# tick-display-mk-4-mini.net
KiCad netlist of a schematic drawn in EAGLE
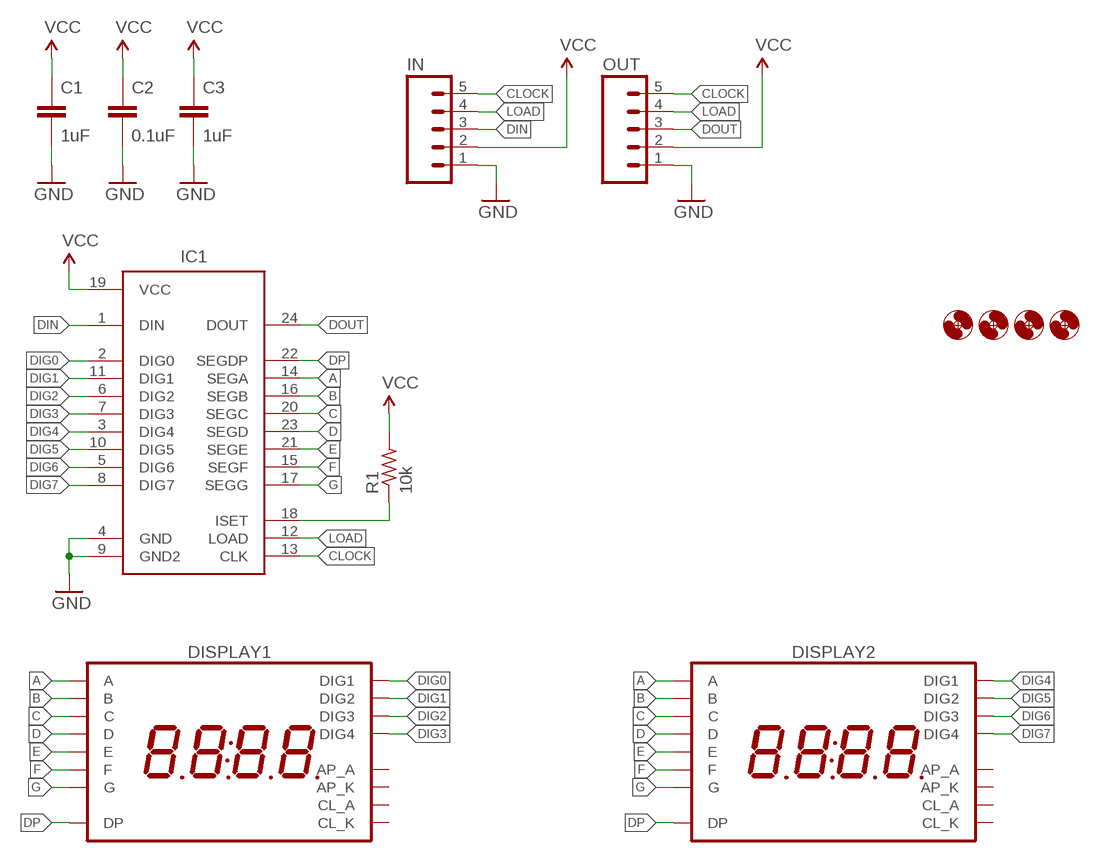
[diagram p0: schematic, sheet 1]

(export (version "E")
  (design (tool "Eeschema 10.0.6"))
  (components
    (comp (ref "C1")
      (value "1uF")
      (footprint "eagle-import:C025-024X044")
      (libsource (lib "eagle-import") (part "CAPACITOR-CERAMIC025-024X044"))
    )
    (comp (ref "C2")
      (value "0.1uF")
      (footprint "eagle-import:C025-024X044")
      (libsource (lib "eagle-import") (part "CAPACITOR-CERAMIC025-024X044"))
    )
    (comp (ref "C3")
      (value "1uF")
      (footprint "eagle-import:C025-024X044")
      (libsource (lib "eagle-import") (part "CAPACITOR-CERAMIC025-024X044"))
    )
    (comp (ref "DISPLAY1")
      (value "7SEG_4DIGIT_10MM")
      (footprint "eagle-import:7SEG_4DIG_10MM")
      (libsource (lib "eagle-import") (part "7SEG_4DIGIT_10MM"))
    )
    (comp (ref "DISPLAY2")
      (value "7SEG_4DIGIT_10MM")
      (footprint "eagle-import:7SEG_4DIG_10MM")
      (libsource (lib "eagle-import") (part "7SEG_4DIGIT_10MM"))
    )
    (comp (ref "H1")
      (value "HOLE#2")
      (footprint "eagle-import:HOLE-#2")
      (libsource (lib "eagle-import") (part "HOLE#2"))
    )
    (comp (ref "H2")
      (value "HOLE#2")
      (footprint "eagle-import:HOLE-#2")
      (libsource (lib "eagle-import") (part "HOLE#2"))
    )
    (comp (ref "H3")
      (value "HOLE#2")
      (footprint "eagle-import:HOLE-#2")
      (libsource (lib "eagle-import") (part "HOLE#2"))
    )
    (comp (ref "H4")
      (value "HOLE#2")
      (footprint "eagle-import:HOLE-#2")
      (libsource (lib "eagle-import") (part "HOLE#2"))
    )
    (comp (ref "IC1")
      (value "MAX7219DIP")
      (footprint "eagle-import:DIL24")
      (libsource (lib "eagle-import") (part "MAX7219DIP"))
    )
    (comp (ref "IN")
      (value "M05PTH")
      (footprint "eagle-import:1X05")
      (libsource (lib "eagle-import") (part "M05PTH"))
    )
    (comp (ref "OUT")
      (value "M05PTH")
      (footprint "eagle-import:1X05")
      (libsource (lib "eagle-import") (part "M05PTH"))
    )
    (comp (ref "R1")
      (value "10k")
      (footprint "eagle-import:RESISTOR-AXIAL-PTH-7.68MM")
      (libsource (lib "eagle-import") (part "RESISTORPTH-AXIAL-7.68MM"))
    )
  )
  (nets
    (net (code "1") (name "A") (class "Default")
      (node (ref "DISPLAY1") (pin "14") (pinfunction "A_14") (pintype "passive"))
      (node (ref "DISPLAY2") (pin "14") (pinfunction "A_14") (pintype "passive"))
      (node (ref "IC1") (pin "14") (pinfunction "SEGA_14") (pintype "bidirectional"))
    )
    (net (code "2") (name "B") (class "Default")
      (node (ref "DISPLAY1") (pin "16") (pinfunction "B_16") (pintype "passive"))
      (node (ref "DISPLAY2") (pin "16") (pinfunction "B_16") (pintype "passive"))
      (node (ref "IC1") (pin "16") (pinfunction "SEGB_16") (pintype "bidirectional"))
    )
    (net (code "3") (name "C") (class "Default")
      (node (ref "DISPLAY1") (pin "13") (pinfunction "C_13") (pintype "passive"))
      (node (ref "DISPLAY2") (pin "13") (pinfunction "C_13") (pintype "passive"))
      (node (ref "IC1") (pin "20") (pinfunction "SEGC_20") (pintype "bidirectional"))
    )
    (net (code "4") (name "CLOCK") (class "Default")
      (node (ref "IC1") (pin "13") (pinfunction "CLK_13") (pintype "bidirectional"))
      (node (ref "IN") (pin "5") (pinfunction "5_5") (pintype "passive"))
      (node (ref "OUT") (pin "5") (pinfunction "5_5") (pintype "passive"))
    )
    (net (code "5") (name "D") (class "Default")
      (node (ref "DISPLAY1") (pin "3") (pinfunction "D_3") (pintype "passive"))
      (node (ref "DISPLAY2") (pin "3") (pinfunction "D_3") (pintype "passive"))
      (node (ref "IC1") (pin "23") (pinfunction "SEGD_23") (pintype "bidirectional"))
    )
    (net (code "6") (name "DIG0") (class "Default")
      (node (ref "DISPLAY1") (pin "1") (pinfunction "DIG1_1") (pintype "passive"))
      (node (ref "IC1") (pin "2") (pinfunction "DIG0_2") (pintype "bidirectional"))
    )
    (net (code "7") (name "DIG1") (class "Default")
      (node (ref "DISPLAY1") (pin "2") (pinfunction "DIG2_2") (pintype "passive"))
      (node (ref "IC1") (pin "11") (pinfunction "DIG1_11") (pintype "bidirectional"))
    )
    (net (code "8") (name "DIG2") (class "Default")
      (node (ref "DISPLAY1") (pin "6") (pinfunction "DIG3_6") (pintype "passive"))
      (node (ref "IC1") (pin "6") (pinfunction "DIG2_6") (pintype "bidirectional"))
    )
    (net (code "9") (name "DIG3") (class "Default")
      (node (ref "DISPLAY1") (pin "8") (pinfunction "DIG4_8") (pintype "passive"))
      (node (ref "IC1") (pin "7") (pinfunction "DIG3_7") (pintype "bidirectional"))
    )
    (net (code "10") (name "DIG4") (class "Default")
      (node (ref "DISPLAY2") (pin "1") (pinfunction "DIG1_1") (pintype "passive"))
      (node (ref "IC1") (pin "3") (pinfunction "DIG4_3") (pintype "bidirectional"))
    )
    (net (code "11") (name "DIG5") (class "Default")
      (node (ref "DISPLAY2") (pin "2") (pinfunction "DIG2_2") (pintype "passive"))
      (node (ref "IC1") (pin "10") (pinfunction "DIG5_10") (pintype "bidirectional"))
    )
    (net (code "12") (name "DIG6") (class "Default")
      (node (ref "DISPLAY2") (pin "6") (pinfunction "DIG3_6") (pintype "passive"))
      (node (ref "IC1") (pin "5") (pinfunction "DIG6_5") (pintype "bidirectional"))
    )
    (net (code "13") (name "DIG7") (class "Default")
      (node (ref "DISPLAY2") (pin "8") (pinfunction "DIG4_8") (pintype "passive"))
      (node (ref "IC1") (pin "8") (pinfunction "DIG7_8") (pintype "bidirectional"))
    )
    (net (code "14") (name "DIN") (class "Default")
      (node (ref "IC1") (pin "1") (pinfunction "DIN_1") (pintype "bidirectional"))
      (node (ref "IN") (pin "3") (pinfunction "3_3") (pintype "passive"))
    )
    (net (code "15") (name "DOUT") (class "Default")
      (node (ref "IC1") (pin "24") (pinfunction "DOUT_24") (pintype "bidirectional"))
      (node (ref "OUT") (pin "3") (pinfunction "3_3") (pintype "passive"))
    )
    (net (code "16") (name "DP") (class "Default")
      (node (ref "DISPLAY1") (pin "7") (pinfunction "DP_7") (pintype "passive"))
      (node (ref "DISPLAY2") (pin "7") (pinfunction "DP_7") (pintype "passive"))
      (node (ref "IC1") (pin "22") (pinfunction "SEGDP_22") (pintype "bidirectional"))
    )
    (net (code "17") (name "E") (class "Default")
      (node (ref "DISPLAY1") (pin "5") (pinfunction "E_5") (pintype "passive"))
      (node (ref "DISPLAY2") (pin "5") (pinfunction "E_5") (pintype "passive"))
      (node (ref "IC1") (pin "21") (pinfunction "SEGE_21") (pintype "bidirectional"))
    )
    (net (code "18") (name "F") (class "Default")
      (node (ref "DISPLAY1") (pin "11") (pinfunction "F_11") (pintype "passive"))
      (node (ref "DISPLAY2") (pin "11") (pinfunction "F_11") (pintype "passive"))
      (node (ref "IC1") (pin "15") (pinfunction "SEGF_15") (pintype "bidirectional"))
    )
    (net (code "19") (name "G") (class "Default")
      (node (ref "DISPLAY1") (pin "15") (pinfunction "G_15") (pintype "passive"))
      (node (ref "DISPLAY2") (pin "15") (pinfunction "G_15") (pintype "passive"))
      (node (ref "IC1") (pin "17") (pinfunction "SEGG_17") (pintype "bidirectional"))
    )
    (net (code "20") (name "GND") (class "Default")
      (node (ref "C1") (pin "2") (pinfunction "2_2") (pintype "passive"))
      (node (ref "C2") (pin "2") (pinfunction "2_2") (pintype "passive"))
      (node (ref "C3") (pin "2") (pinfunction "2_2") (pintype "passive"))
      (node (ref "IC1") (pin "4") (pinfunction "GND_4") (pintype "bidirectional"))
      (node (ref "IC1") (pin "9") (pinfunction "GND2_9") (pintype "bidirectional"))
      (node (ref "IN") (pin "1") (pinfunction "1_1") (pintype "passive"))
      (node (ref "OUT") (pin "1") (pinfunction "1_1") (pintype "passive"))
    )
    (net (code "21") (name "LOAD") (class "Default")
      (node (ref "IC1") (pin "12") (pinfunction "LOAD_12") (pintype "bidirectional"))
      (node (ref "IN") (pin "4") (pinfunction "4_4") (pintype "passive"))
      (node (ref "OUT") (pin "4") (pinfunction "4_4") (pintype "passive"))
    )
    (net (code "22") (name "Net-(IC1-ISET)") (class "Default")
      (node (ref "IC1") (pin "18") (pinfunction "ISET_18") (pintype "bidirectional"))
      (node (ref "R1") (pin "P$1") (pinfunction "1_P$1") (pintype "passive"))
    )
    (net (code "23") (name "VCC") (class "Default")
      (node (ref "C1") (pin "1") (pinfunction "1_1") (pintype "passive"))
      (node (ref "C2") (pin "1") (pinfunction "1_1") (pintype "passive"))
      (node (ref "C3") (pin "1") (pinfunction "1_1") (pintype "passive"))
      (node (ref "IC1") (pin "19") (pinfunction "VCC_19") (pintype "bidirectional"))
      (node (ref "IN") (pin "2") (pinfunction "2_2") (pintype "passive"))
      (node (ref "OUT") (pin "2") (pinfunction "2_2") (pintype "passive"))
      (node (ref "R1") (pin "P$2") (pinfunction "2_P$2") (pintype "passive"))
    )
    (net (code "24") (name "unconnected-(DISPLAY1-AP_A-Pad10)") (class "Default")
      (node (ref "DISPLAY1") (pin "10") (pinfunction "AP_A_10") (pintype "bidirectional"))
    )
    (net (code "25") (name "unconnected-(DISPLAY1-AP_K-Pad9)") (class "Default")
      (node (ref "DISPLAY1") (pin "9") (pinfunction "AP_K_9") (pintype "bidirectional"))
    )
    (net (code "26") (name "unconnected-(DISPLAY1-CL_A-Pad4)") (class "Default")
      (node (ref "DISPLAY1") (pin "4") (pinfunction "CL_A_4") (pintype "passive"))
    )
    (net (code "27") (name "unconnected-(DISPLAY1-CL_K-Pad12)") (class "Default")
      (node (ref "DISPLAY1") (pin "12") (pinfunction "CL_K_12") (pintype "passive"))
    )
    (net (code "28") (name "unconnected-(DISPLAY2-AP_A-Pad10)") (class "Default")
      (node (ref "DISPLAY2") (pin "10") (pinfunction "AP_A_10") (pintype "bidirectional"))
    )
    (net (code "29") (name "unconnected-(DISPLAY2-AP_K-Pad9)") (class "Default")
      (node (ref "DISPLAY2") (pin "9") (pinfunction "AP_K_9") (pintype "bidirectional"))
    )
    (net (code "30") (name "unconnected-(DISPLAY2-CL_A-Pad4)") (class "Default")
      (node (ref "DISPLAY2") (pin "4") (pinfunction "CL_A_4") (pintype "passive"))
    )
    (net (code "31") (name "unconnected-(DISPLAY2-CL_K-Pad12)") (class "Default")
      (node (ref "DISPLAY2") (pin "12") (pinfunction "CL_K_12") (pintype "passive"))
    )
  )
)
